# schmitt_rev2.net
KiCad netlist of a schematic drawn in EAGLE
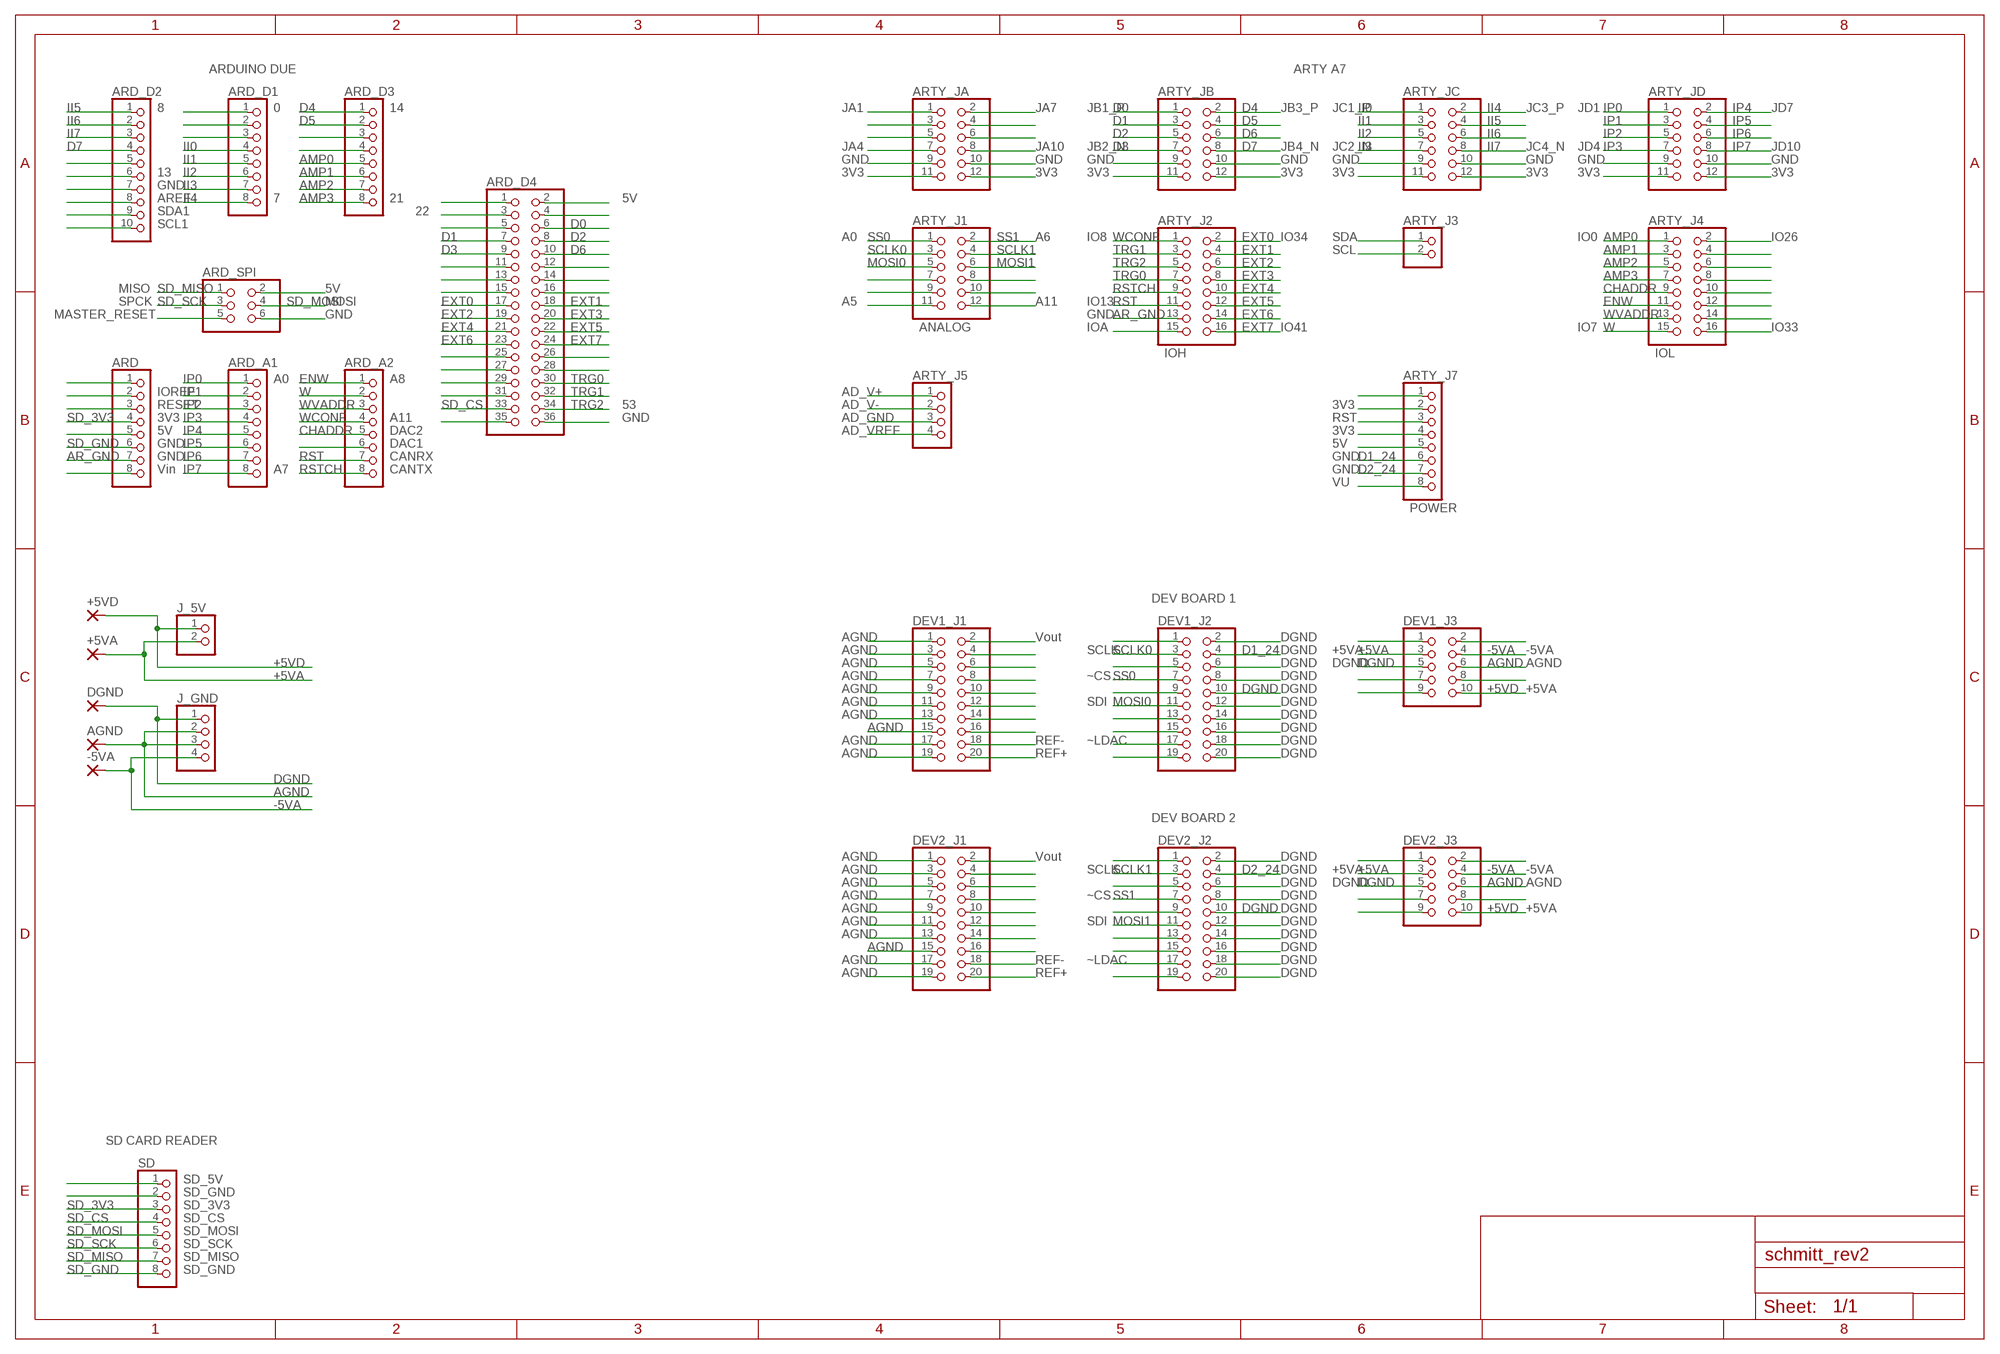
[diagram p0: schematic, sheet 1]

(export (version "E")
  (design (tool "Eeschema 10.0.6"))
  (components
    (comp (ref "+5VA")
      (value "2,15/1,0")
      (footprint "eagle-import:2,15_1,0")
      (libsource (lib "eagle-import") (part "2,15/1,0"))
    )
    (comp (ref "+5VD")
      (value "2,15/1,0")
      (footprint "eagle-import:2,15_1,0")
      (libsource (lib "eagle-import") (part "2,15/1,0"))
    )
    (comp (ref "-5VA")
      (value "2,15/1,0")
      (footprint "eagle-import:2,15_1,0")
      (libsource (lib "eagle-import") (part "2,15/1,0"))
    )
    (comp (ref "AGND")
      (value "2,15/1,0")
      (footprint "eagle-import:2,15_1,0")
      (libsource (lib "eagle-import") (part "2,15/1,0"))
    )
    (comp (ref "ARD")
      (value "PINHD-1X8")
      (footprint "eagle-import:1X08")
      (libsource (lib "eagle-import") (part "PINHD-1X8"))
    )
    (comp (ref "ARD_A1")
      (value "PINHD-1X8")
      (footprint "eagle-import:1X08")
      (libsource (lib "eagle-import") (part "PINHD-1X8"))
    )
    (comp (ref "ARD_A2")
      (value "PINHD-1X8")
      (footprint "eagle-import:1X08")
      (libsource (lib "eagle-import") (part "PINHD-1X8"))
    )
    (comp (ref "ARD_D1")
      (value "PINHD-1X8")
      (footprint "eagle-import:1X08")
      (libsource (lib "eagle-import") (part "PINHD-1X8"))
    )
    (comp (ref "ARD_D2")
      (value "PINHD-1X10")
      (footprint "eagle-import:1X10")
      (libsource (lib "eagle-import") (part "PINHD-1X10"))
    )
    (comp (ref "ARD_D3")
      (value "PINHD-1X8")
      (footprint "eagle-import:1X08")
      (libsource (lib "eagle-import") (part "PINHD-1X8"))
    )
    (comp (ref "ARD_D4")
      (value "PINHD-2X18")
      (footprint "eagle-import:2X18")
      (libsource (lib "eagle-import") (part "PINHD-2X18"))
    )
    (comp (ref "ARD_SPI")
      (value "PINHD-2X3")
      (footprint "eagle-import:2X03")
      (libsource (lib "eagle-import") (part "PINHD-2X3"))
    )
    (comp (ref "ARTY_J1")
      (value "PINHD-2X6")
      (footprint "eagle-import:2X06")
      (libsource (lib "eagle-import") (part "PINHD-2X6"))
    )
    (comp (ref "ARTY_J2")
      (value "PINHD-2X8")
      (footprint "eagle-import:2X08")
      (libsource (lib "eagle-import") (part "PINHD-2X8"))
    )
    (comp (ref "ARTY_J3")
      (value "PINHD-1X2")
      (footprint "eagle-import:1X02")
      (libsource (lib "eagle-import") (part "PINHD-1X2"))
    )
    (comp (ref "ARTY_J4")
      (value "PINHD-2X8")
      (footprint "eagle-import:2X08")
      (libsource (lib "eagle-import") (part "PINHD-2X8"))
    )
    (comp (ref "ARTY_J5")
      (value "PINHD-1X4")
      (footprint "eagle-import:1X04")
      (libsource (lib "eagle-import") (part "PINHD-1X4"))
    )
    (comp (ref "ARTY_J7")
      (value "PINHD-1X8")
      (footprint "eagle-import:1X08")
      (libsource (lib "eagle-import") (part "PINHD-1X8"))
    )
    (comp (ref "ARTY_JA")
      (value "PINHD-2X6")
      (footprint "eagle-import:2X06")
      (libsource (lib "eagle-import") (part "PINHD-2X6"))
    )
    (comp (ref "ARTY_JB")
      (value "PINHD-2X6")
      (footprint "eagle-import:2X06")
      (libsource (lib "eagle-import") (part "PINHD-2X6"))
    )
    (comp (ref "ARTY_JC")
      (value "PINHD-2X6")
      (footprint "eagle-import:2X06")
      (libsource (lib "eagle-import") (part "PINHD-2X6"))
    )
    (comp (ref "ARTY_JD")
      (value "PINHD-2X6")
      (footprint "eagle-import:2X06")
      (libsource (lib "eagle-import") (part "PINHD-2X6"))
    )
    (comp (ref "DEV1_J1")
      (value "PINHD-2X10")
      (footprint "eagle-import:2X10")
      (libsource (lib "eagle-import") (part "PINHD-2X10"))
    )
    (comp (ref "DEV1_J2")
      (value "PINHD-2X10")
      (footprint "eagle-import:2X10")
      (libsource (lib "eagle-import") (part "PINHD-2X10"))
    )
    (comp (ref "DEV1_J3")
      (value "PINHD-2X5")
      (footprint "eagle-import:2X05")
      (libsource (lib "eagle-import") (part "PINHD-2X5"))
    )
    (comp (ref "DEV2_J1")
      (value "PINHD-2X10")
      (footprint "eagle-import:2X10")
      (libsource (lib "eagle-import") (part "PINHD-2X10"))
    )
    (comp (ref "DEV2_J2")
      (value "PINHD-2X10")
      (footprint "eagle-import:2X10")
      (libsource (lib "eagle-import") (part "PINHD-2X10"))
    )
    (comp (ref "DEV2_J3")
      (value "PINHD-2X5")
      (footprint "eagle-import:2X05")
      (libsource (lib "eagle-import") (part "PINHD-2X5"))
    )
    (comp (ref "DGND")
      (value "2,15/1,0")
      (footprint "eagle-import:2,15_1,0")
      (libsource (lib "eagle-import") (part "2,15/1,0"))
    )
    (comp (ref "J_5V")
      (value "PINHD-1X2")
      (footprint "eagle-import:1X02")
      (libsource (lib "eagle-import") (part "PINHD-1X2"))
    )
    (comp (ref "J_GND")
      (value "PINHD-1X4")
      (footprint "eagle-import:1X04")
      (libsource (lib "eagle-import") (part "PINHD-1X4"))
    )
    (comp (ref "SD")
      (value "PINHD-1X8")
      (footprint "eagle-import:1X08")
      (libsource (lib "eagle-import") (part "PINHD-1X8"))
    )
  )
  (nets
    (net (code "1") (name "/+5VA") (class "Default")
      (node (ref "+5VA") (pin "1") (pinfunction "P_1") (pintype "passive"))
      (node (ref "DEV1_J3") (pin "3") (pinfunction "3_3") (pintype "passive"))
      (node (ref "DEV2_J3") (pin "3") (pinfunction "3_3") (pintype "passive"))
      (node (ref "J_5V") (pin "2") (pinfunction "2_2") (pintype "passive"))
    )
    (net (code "2") (name "/+5VD") (class "Default")
      (node (ref "+5VD") (pin "1") (pinfunction "P_1") (pintype "passive"))
      (node (ref "DEV1_J3") (pin "10") (pinfunction "10_10") (pintype "passive"))
      (node (ref "DEV2_J3") (pin "10") (pinfunction "10_10") (pintype "passive"))
      (node (ref "J_5V") (pin "1") (pinfunction "1_1") (pintype "passive"))
    )
    (net (code "3") (name "/-5VA") (class "Default")
      (node (ref "-5VA") (pin "1") (pinfunction "P_1") (pintype "passive"))
      (node (ref "DEV1_J3") (pin "4") (pinfunction "4_4") (pintype "passive"))
      (node (ref "DEV2_J3") (pin "4") (pinfunction "4_4") (pintype "passive"))
      (node (ref "J_GND") (pin "4") (pinfunction "4_4") (pintype "passive"))
    )
    (net (code "4") (name "/AGND") (class "Default")
      (node (ref "AGND") (pin "1") (pinfunction "P_1") (pintype "passive"))
      (node (ref "DEV1_J1") (pin "15") (pinfunction "15_15") (pintype "passive"))
      (node (ref "DEV1_J3") (pin "6") (pinfunction "6_6") (pintype "passive"))
      (node (ref "DEV2_J1") (pin "15") (pinfunction "15_15") (pintype "passive"))
      (node (ref "DEV2_J3") (pin "6") (pinfunction "6_6") (pintype "passive"))
      (node (ref "J_GND") (pin "2") (pinfunction "2_2") (pintype "passive"))
      (node (ref "J_GND") (pin "3") (pinfunction "3_3") (pintype "passive"))
    )
    (net (code "5") (name "/AMP0") (class "Default")
      (node (ref "ARD_D3") (pin "5") (pinfunction "5_5") (pintype "passive"))
      (node (ref "ARTY_J4") (pin "1") (pinfunction "1_1") (pintype "passive"))
    )
    (net (code "6") (name "/AMP1") (class "Default")
      (node (ref "ARD_D3") (pin "6") (pinfunction "6_6") (pintype "passive"))
      (node (ref "ARTY_J4") (pin "3") (pinfunction "3_3") (pintype "passive"))
    )
    (net (code "7") (name "/AMP2") (class "Default")
      (node (ref "ARD_D3") (pin "7") (pinfunction "7_7") (pintype "passive"))
      (node (ref "ARTY_J4") (pin "5") (pinfunction "5_5") (pintype "passive"))
    )
    (net (code "8") (name "/AMP3") (class "Default")
      (node (ref "ARD_D3") (pin "8") (pinfunction "8_8") (pintype "passive"))
      (node (ref "ARTY_J4") (pin "7") (pinfunction "7_7") (pintype "passive"))
    )
    (net (code "9") (name "/AR_GND") (class "Default")
      (node (ref "ARD") (pin "7") (pinfunction "7_7") (pintype "passive"))
      (node (ref "ARTY_J2") (pin "13") (pinfunction "13_13") (pintype "passive"))
    )
    (net (code "10") (name "/CHADDR") (class "Default")
      (node (ref "ARD_A2") (pin "5") (pinfunction "5_5") (pintype "passive"))
      (node (ref "ARTY_J4") (pin "9") (pinfunction "9_9") (pintype "passive"))
    )
    (net (code "11") (name "/D0") (class "Default")
      (node (ref "ARD_D4") (pin "6") (pinfunction "6_6") (pintype "passive"))
      (node (ref "ARTY_JB") (pin "1") (pinfunction "1_1") (pintype "passive"))
    )
    (net (code "12") (name "/D1") (class "Default")
      (node (ref "ARD_D4") (pin "7") (pinfunction "7_7") (pintype "passive"))
      (node (ref "ARTY_JB") (pin "3") (pinfunction "3_3") (pintype "passive"))
    )
    (net (code "13") (name "/D1_24") (class "Default")
      (node (ref "ARTY_J7") (pin "6") (pinfunction "6_6") (pintype "passive"))
      (node (ref "DEV1_J2") (pin "4") (pinfunction "4_4") (pintype "passive"))
    )
    (net (code "14") (name "/D2") (class "Default")
      (node (ref "ARD_D4") (pin "8") (pinfunction "8_8") (pintype "passive"))
      (node (ref "ARTY_JB") (pin "5") (pinfunction "5_5") (pintype "passive"))
    )
    (net (code "15") (name "/D2_24") (class "Default")
      (node (ref "ARTY_J7") (pin "7") (pinfunction "7_7") (pintype "passive"))
      (node (ref "DEV2_J2") (pin "4") (pinfunction "4_4") (pintype "passive"))
    )
    (net (code "16") (name "/D3") (class "Default")
      (node (ref "ARD_D4") (pin "9") (pinfunction "9_9") (pintype "passive"))
      (node (ref "ARTY_JB") (pin "7") (pinfunction "7_7") (pintype "passive"))
    )
    (net (code "17") (name "/D4") (class "Default")
      (node (ref "ARD_D3") (pin "1") (pinfunction "1_1") (pintype "passive"))
      (node (ref "ARTY_JB") (pin "2") (pinfunction "2_2") (pintype "passive"))
    )
    (net (code "18") (name "/D5") (class "Default")
      (node (ref "ARD_D3") (pin "2") (pinfunction "2_2") (pintype "passive"))
      (node (ref "ARTY_JB") (pin "4") (pinfunction "4_4") (pintype "passive"))
    )
    (net (code "19") (name "/D6") (class "Default")
      (node (ref "ARD_D4") (pin "10") (pinfunction "10_10") (pintype "passive"))
      (node (ref "ARTY_JB") (pin "6") (pinfunction "6_6") (pintype "passive"))
    )
    (net (code "20") (name "/D7") (class "Default")
      (node (ref "ARD_D2") (pin "4") (pinfunction "4_4") (pintype "passive"))
      (node (ref "ARTY_JB") (pin "8") (pinfunction "8_8") (pintype "passive"))
    )
    (net (code "21") (name "/DGND") (class "Default")
      (node (ref "DEV1_J2") (pin "10") (pinfunction "10_10") (pintype "passive"))
      (node (ref "DEV1_J3") (pin "5") (pinfunction "5_5") (pintype "passive"))
      (node (ref "DEV2_J2") (pin "10") (pinfunction "10_10") (pintype "passive"))
      (node (ref "DEV2_J3") (pin "5") (pinfunction "5_5") (pintype "passive"))
      (node (ref "DGND") (pin "1") (pinfunction "P_1") (pintype "passive"))
      (node (ref "J_GND") (pin "1") (pinfunction "1_1") (pintype "passive"))
    )
    (net (code "22") (name "/ENW") (class "Default")
      (node (ref "ARD_A2") (pin "1") (pinfunction "1_1") (pintype "passive"))
      (node (ref "ARTY_J4") (pin "11") (pinfunction "11_11") (pintype "passive"))
    )
    (net (code "23") (name "/EXT0") (class "Default")
      (node (ref "ARD_D4") (pin "17") (pinfunction "17_17") (pintype "passive"))
      (node (ref "ARTY_J2") (pin "2") (pinfunction "2_2") (pintype "passive"))
    )
    (net (code "24") (name "/EXT1") (class "Default")
      (node (ref "ARD_D4") (pin "18") (pinfunction "18_18") (pintype "passive"))
      (node (ref "ARTY_J2") (pin "4") (pinfunction "4_4") (pintype "passive"))
    )
    (net (code "25") (name "/EXT2") (class "Default")
      (node (ref "ARD_D4") (pin "19") (pinfunction "19_19") (pintype "passive"))
      (node (ref "ARTY_J2") (pin "6") (pinfunction "6_6") (pintype "passive"))
    )
    (net (code "26") (name "/EXT3") (class "Default")
      (node (ref "ARD_D4") (pin "20") (pinfunction "20_20") (pintype "passive"))
      (node (ref "ARTY_J2") (pin "8") (pinfunction "8_8") (pintype "passive"))
    )
    (net (code "27") (name "/EXT4") (class "Default")
      (node (ref "ARD_D4") (pin "21") (pinfunction "21_21") (pintype "passive"))
      (node (ref "ARTY_J2") (pin "10") (pinfunction "10_10") (pintype "passive"))
    )
    (net (code "28") (name "/EXT5") (class "Default")
      (node (ref "ARD_D4") (pin "22") (pinfunction "22_22") (pintype "passive"))
      (node (ref "ARTY_J2") (pin "12") (pinfunction "12_12") (pintype "passive"))
    )
    (net (code "29") (name "/EXT6") (class "Default")
      (node (ref "ARD_D4") (pin "23") (pinfunction "23_23") (pintype "passive"))
      (node (ref "ARTY_J2") (pin "14") (pinfunction "14_14") (pintype "passive"))
    )
    (net (code "30") (name "/EXT7") (class "Default")
      (node (ref "ARD_D4") (pin "24") (pinfunction "24_24") (pintype "passive"))
      (node (ref "ARTY_J2") (pin "16") (pinfunction "16_16") (pintype "passive"))
    )
    (net (code "31") (name "/II0") (class "Default")
      (node (ref "ARD_D1") (pin "4") (pinfunction "4_4") (pintype "passive"))
      (node (ref "ARTY_JC") (pin "1") (pinfunction "1_1") (pintype "passive"))
    )
    (net (code "32") (name "/II1") (class "Default")
      (node (ref "ARD_D1") (pin "5") (pinfunction "5_5") (pintype "passive"))
      (node (ref "ARTY_JC") (pin "3") (pinfunction "3_3") (pintype "passive"))
    )
    (net (code "33") (name "/II2") (class "Default")
      (node (ref "ARD_D1") (pin "6") (pinfunction "6_6") (pintype "passive"))
      (node (ref "ARTY_JC") (pin "5") (pinfunction "5_5") (pintype "passive"))
    )
    (net (code "34") (name "/II3") (class "Default")
      (node (ref "ARD_D1") (pin "7") (pinfunction "7_7") (pintype "passive"))
      (node (ref "ARTY_JC") (pin "7") (pinfunction "7_7") (pintype "passive"))
    )
    (net (code "35") (name "/II4") (class "Default")
      (node (ref "ARD_D1") (pin "8") (pinfunction "8_8") (pintype "passive"))
      (node (ref "ARTY_JC") (pin "2") (pinfunction "2_2") (pintype "passive"))
    )
    (net (code "36") (name "/II5") (class "Default")
      (node (ref "ARD_D2") (pin "1") (pinfunction "1_1") (pintype "passive"))
      (node (ref "ARTY_JC") (pin "4") (pinfunction "4_4") (pintype "passive"))
    )
    (net (code "37") (name "/II6") (class "Default")
      (node (ref "ARD_D2") (pin "2") (pinfunction "2_2") (pintype "passive"))
      (node (ref "ARTY_JC") (pin "6") (pinfunction "6_6") (pintype "passive"))
    )
    (net (code "38") (name "/II7") (class "Default")
      (node (ref "ARD_D2") (pin "3") (pinfunction "3_3") (pintype "passive"))
      (node (ref "ARTY_JC") (pin "8") (pinfunction "8_8") (pintype "passive"))
    )
    (net (code "39") (name "/IP0") (class "Default")
      (node (ref "ARD_A1") (pin "1") (pinfunction "1_1") (pintype "passive"))
      (node (ref "ARTY_JD") (pin "1") (pinfunction "1_1") (pintype "passive"))
    )
    (net (code "40") (name "/IP1") (class "Default")
      (node (ref "ARD_A1") (pin "2") (pinfunction "2_2") (pintype "passive"))
      (node (ref "ARTY_JD") (pin "3") (pinfunction "3_3") (pintype "passive"))
    )
    (net (code "41") (name "/IP2") (class "Default")
      (node (ref "ARD_A1") (pin "3") (pinfunction "3_3") (pintype "passive"))
      (node (ref "ARTY_JD") (pin "5") (pinfunction "5_5") (pintype "passive"))
    )
    (net (code "42") (name "/IP3") (class "Default")
      (node (ref "ARD_A1") (pin "4") (pinfunction "4_4") (pintype "passive"))
      (node (ref "ARTY_JD") (pin "7") (pinfunction "7_7") (pintype "passive"))
    )
    (net (code "43") (name "/IP4") (class "Default")
      (node (ref "ARD_A1") (pin "5") (pinfunction "5_5") (pintype "passive"))
      (node (ref "ARTY_JD") (pin "2") (pinfunction "2_2") (pintype "passive"))
    )
    (net (code "44") (name "/IP5") (class "Default")
      (node (ref "ARD_A1") (pin "6") (pinfunction "6_6") (pintype "passive"))
      (node (ref "ARTY_JD") (pin "4") (pinfunction "4_4") (pintype "passive"))
    )
    (net (code "45") (name "/IP6") (class "Default")
      (node (ref "ARD_A1") (pin "7") (pinfunction "7_7") (pintype "passive"))
      (node (ref "ARTY_JD") (pin "6") (pinfunction "6_6") (pintype "passive"))
    )
    (net (code "46") (name "/IP7") (class "Default")
      (node (ref "ARD_A1") (pin "8") (pinfunction "8_8") (pintype "passive"))
      (node (ref "ARTY_JD") (pin "8") (pinfunction "8_8") (pintype "passive"))
    )
    (net (code "47") (name "/MOSI0") (class "Default")
      (node (ref "ARTY_J1") (pin "5") (pinfunction "5_5") (pintype "passive"))
      (node (ref "DEV1_J2") (pin "11") (pinfunction "11_11") (pintype "passive"))
    )
    (net (code "48") (name "/MOSI1") (class "Default")
      (node (ref "ARTY_J1") (pin "6") (pinfunction "6_6") (pintype "passive"))
      (node (ref "DEV2_J2") (pin "11") (pinfunction "11_11") (pintype "passive"))
    )
    (net (code "49") (name "/RST") (class "Default")
      (node (ref "ARD_A2") (pin "7") (pinfunction "7_7") (pintype "passive"))
      (node (ref "ARTY_J2") (pin "11") (pinfunction "11_11") (pintype "passive"))
    )
    (net (code "50") (name "/RSTCH") (class "Default")
      (node (ref "ARD_A2") (pin "8") (pinfunction "8_8") (pintype "passive"))
      (node (ref "ARTY_J2") (pin "9") (pinfunction "9_9") (pintype "passive"))
    )
    (net (code "51") (name "/SCLK0") (class "Default")
      (node (ref "ARTY_J1") (pin "3") (pinfunction "3_3") (pintype "passive"))
      (node (ref "DEV1_J2") (pin "3") (pinfunction "3_3") (pintype "passive"))
    )
    (net (code "52") (name "/SCLK1") (class "Default")
      (node (ref "ARTY_J1") (pin "4") (pinfunction "4_4") (pintype "passive"))
      (node (ref "DEV2_J2") (pin "3") (pinfunction "3_3") (pintype "passive"))
    )
    (net (code "53") (name "/SD_3V3") (class "Default")
      (node (ref "ARD") (pin "4") (pinfunction "4_4") (pintype "passive"))
      (node (ref "SD") (pin "3") (pinfunction "3_3") (pintype "passive"))
    )
    (net (code "54") (name "/SD_CS") (class "Default")
      (node (ref "ARD_D4") (pin "33") (pinfunction "33_33") (pintype "passive"))
      (node (ref "SD") (pin "4") (pinfunction "4_4") (pintype "passive"))
    )
    (net (code "55") (name "/SD_GND") (class "Default")
      (node (ref "ARD") (pin "6") (pinfunction "6_6") (pintype "passive"))
      (node (ref "SD") (pin "8") (pinfunction "8_8") (pintype "passive"))
    )
    (net (code "56") (name "/SD_MISO") (class "Default")
      (node (ref "ARD_SPI") (pin "1") (pinfunction "1_1") (pintype "passive"))
      (node (ref "SD") (pin "7") (pinfunction "7_7") (pintype "passive"))
    )
    (net (code "57") (name "/SD_MOSI") (class "Default")
      (node (ref "ARD_SPI") (pin "4") (pinfunction "4_4") (pintype "passive"))
      (node (ref "SD") (pin "5") (pinfunction "5_5") (pintype "passive"))
    )
    (net (code "58") (name "/SD_SCK") (class "Default")
      (node (ref "ARD_SPI") (pin "3") (pinfunction "3_3") (pintype "passive"))
      (node (ref "SD") (pin "6") (pinfunction "6_6") (pintype "passive"))
    )
    (net (code "59") (name "/SS0") (class "Default")
      (node (ref "ARTY_J1") (pin "1") (pinfunction "1_1") (pintype "passive"))
      (node (ref "DEV1_J2") (pin "7") (pinfunction "7_7") (pintype "passive"))
    )
    (net (code "60") (name "/SS1") (class "Default")
      (node (ref "ARTY_J1") (pin "2") (pinfunction "2_2") (pintype "passive"))
      (node (ref "DEV2_J2") (pin "7") (pinfunction "7_7") (pintype "passive"))
    )
    (net (code "61") (name "/TRG0") (class "Default")
      (node (ref "ARD_D4") (pin "30") (pinfunction "30_30") (pintype "passive"))
      (node (ref "ARTY_J2") (pin "7") (pinfunction "7_7") (pintype "passive"))
    )
    (net (code "62") (name "/TRG1") (class "Default")
      (node (ref "ARD_D4") (pin "32") (pinfunction "32_32") (pintype "passive"))
      (node (ref "ARTY_J2") (pin "3") (pinfunction "3_3") (pintype "passive"))
    )
    (net (code "63") (name "/TRG2") (class "Default")
      (node (ref "ARD_D4") (pin "34") (pinfunction "34_34") (pintype "passive"))
      (node (ref "ARTY_J2") (pin "5") (pinfunction "5_5") (pintype "passive"))
    )
    (net (code "64") (name "/W") (class "Default")
      (node (ref "ARD_A2") (pin "2") (pinfunction "2_2") (pintype "passive"))
      (node (ref "ARTY_J4") (pin "15") (pinfunction "15_15") (pintype "passive"))
    )
    (net (code "65") (name "/WCONF") (class "Default")
      (node (ref "ARD_A2") (pin "4") (pinfunction "4_4") (pintype "passive"))
      (node (ref "ARTY_J2") (pin "1") (pinfunction "1_1") (pintype "passive"))
    )
    (net (code "66") (name "/WVADDR") (class "Default")
      (node (ref "ARD_A2") (pin "3") (pinfunction "3_3") (pintype "passive"))
      (node (ref "ARTY_J4") (pin "13") (pinfunction "13_13") (pintype "passive"))
    )
    (net (code "67") (name "unconnected-(ARD-Pad1)") (class "Default")
      (node (ref "ARD") (pin "1") (pinfunction "1_1") (pintype "passive"))
    )
    (net (code "68") (name "unconnected-(ARD-Pad2)") (class "Default")
      (node (ref "ARD") (pin "2") (pinfunction "2_2") (pintype "passive"))
    )
    (net (code "69") (name "unconnected-(ARD-Pad3)") (class "Default")
      (node (ref "ARD") (pin "3") (pinfunction "3_3") (pintype "passive"))
    )
    (net (code "70") (name "unconnected-(ARD-Pad5)") (class "Default")
      (node (ref "ARD") (pin "5") (pinfunction "5_5") (pintype "passive"))
    )
    (net (code "71") (name "unconnected-(ARD-Pad8)") (class "Default")
      (node (ref "ARD") (pin "8") (pinfunction "8_8") (pintype "passive"))
    )
    (net (code "72") (name "unconnected-(ARD_A2-Pad6)") (class "Default")
      (node (ref "ARD_A2") (pin "6") (pinfunction "6_6") (pintype "passive"))
    )
    (net (code "73") (name "unconnected-(ARD_D1-Pad1)") (class "Default")
      (node (ref "ARD_D1") (pin "1") (pinfunction "1_1") (pintype "passive"))
    )
    (net (code "74") (name "unconnected-(ARD_D1-Pad2)") (class "Default")
      (node (ref "ARD_D1") (pin "2") (pinfunction "2_2") (pintype "passive"))
    )
    (net (code "75") (name "unconnected-(ARD_D1-Pad3)") (class "Default")
      (node (ref "ARD_D1") (pin "3") (pinfunction "3_3") (pintype "passive"))
    )
    (net (code "76") (name "unconnected-(ARD_D2-Pad5)") (class "Default")
      (node (ref "ARD_D2") (pin "5") (pinfunction "5_5") (pintype "passive"))
    )
    (net (code "77") (name "unconnected-(ARD_D2-Pad6)") (class "Default")
      (node (ref "ARD_D2") (pin "6") (pinfunction "6_6") (pintype "passive"))
    )
    (net (code "78") (name "unconnected-(ARD_D2-Pad7)") (class "Default")
      (node (ref "ARD_D2") (pin "7") (pinfunction "7_7") (pintype "passive"))
    )
    (net (code "79") (name "unconnected-(ARD_D2-Pad8)") (class "Default")
      (node (ref "ARD_D2") (pin "8") (pinfunction "8_8") (pintype "passive"))
    )
    (net (code "80") (name "unconnected-(ARD_D2-Pad9)") (class "Default")
      (node (ref "ARD_D2") (pin "9") (pinfunction "9_9") (pintype "passive"))
    )
    (net (code "81") (name "unconnected-(ARD_D2-Pad10)") (class "Default")
      (node (ref "ARD_D2") (pin "10") (pinfunction "10_10") (pintype "passive"))
    )
    (net (code "82") (name "unconnected-(ARD_D3-Pad3)") (class "Default")
      (node (ref "ARD_D3") (pin "3") (pinfunction "3_3") (pintype "passive"))
    )
    (net (code "83") (name "unconnected-(ARD_D3-Pad4)") (class "Default")
      (node (ref "ARD_D3") (pin "4") (pinfunction "4_4") (pintype "passive"))
    )
    (net (code "84") (name "unconnected-(ARD_D4-Pad1)") (class "Default")
      (node (ref "ARD_D4") (pin "1") (pinfunction "1_1") (pintype "passive"))
    )
    (net (code "85") (name "unconnected-(ARD_D4-Pad2)") (class "Default")
      (node (ref "ARD_D4") (pin "2") (pinfunction "2_2") (pintype "passive"))
    )
    (net (code "86") (name "unconnected-(ARD_D4-Pad3)") (class "Default")
      (node (ref "ARD_D4") (pin "3") (pinfunction "3_3") (pintype "passive"))
    )
    (net (code "87") (name "unconnected-(ARD_D4-Pad4)") (class "Default")
      (node (ref "ARD_D4") (pin "4") (pinfunction "4_4") (pintype "passive"))
    )
    (net (code "88") (name "unconnected-(ARD_D4-Pad5)") (class "Default")
      (node (ref "ARD_D4") (pin "5") (pinfunction "5_5") (pintype "passive"))
    )
    (net (code "89") (name "unconnected-(ARD_D4-Pad11)") (class "Default")
      (node (ref "ARD_D4") (pin "11") (pinfunction "11_11") (pintype "passive"))
    )
    (net (code "90") (name "unconnected-(ARD_D4-Pad12)") (class "Default")
      (node (ref "ARD_D4") (pin "12") (pinfunction "12_12") (pintype "passive"))
    )
    (net (code "91") (name "unconnected-(ARD_D4-Pad13)") (class "Default")
      (node (ref "ARD_D4") (pin "13") (pinfunction "13_13") (pintype "passive"))
    )
    (net (code "92") (name "unconnected-(ARD_D4-Pad14)") (class "Default")
      (node (ref "ARD_D4") (pin "14") (pinfunction "14_14") (pintype "passive"))
    )
    (net (code "93") (name "unconnected-(ARD_D4-Pad15)") (class "Default")
      (node (ref "ARD_D4") (pin "15") (pinfunction "15_15") (pintype "passive"))
    )
    (net (code "94") (name "unconnected-(ARD_D4-Pad16)") (class "Default")
      (node (ref "ARD_D4") (pin "16") (pinfunction "16_16") (pintype "passive"))
    )
    (net (code "95") (name "unconnected-(ARD_D4-Pad25)") (class "Default")
      (node (ref "ARD_D4") (pin "25") (pinfunction "25_25") (pintype "passive"))
    )
    (net (code "96") (name "unconnected-(ARD_D4-Pad26)") (class "Default")
      (node (ref "ARD_D4") (pin "26") (pinfunction "26_26") (pintype "passive"))
    )
    (net (code "97") (name "unconnected-(ARD_D4-Pad27)") (class "Default")
      (node (ref "ARD_D4") (pin "27") (pinfunction "27_27") (pintype "passive"))
    )
    (net (code "98") (name "unconnected-(ARD_D4-Pad28)") (class "Default")
      (node (ref "ARD_D4") (pin "28") (pinfunction "28_28") (pintype "passive"))
    )
    (net (code "99") (name "unconnected-(ARD_D4-Pad29)") (class "Default")
      (node (ref "ARD_D4") (pin "29") (pinfunction "29_29") (pintype "passive"))
    )
    (net (code "100") (name "unconnected-(ARD_D4-Pad31)") (class "Default")
      (node (ref "ARD_D4") (pin "31") (pinfunction "31_31") (pintype "passive"))
    )
    (net (code "101") (name "unconnected-(ARD_D4-Pad35)") (class "Default")
      (node (ref "ARD_D4") (pin "35") (pinfunction "35_35") (pintype "passive"))
    )
    (net (code "102") (name "unconnected-(ARD_D4-Pad36)") (class "Default")
      (node (ref "ARD_D4") (pin "36") (pinfunction "36_36") (pintype "passive"))
    )
    (net (code "103") (name "unconnected-(ARD_SPI-Pad2)") (class "Default")
      (node (ref "ARD_SPI") (pin "2") (pinfunction "2_2") (pintype "passive"))
    )
    (net (code "104") (name "unconnected-(ARD_SPI-Pad5)") (class "Default")
      (node (ref "ARD_SPI") (pin "5") (pinfunction "5_5") (pintype "passive"))
    )
    (net (code "105") (name "unconnected-(ARD_SPI-Pad6)") (class "Default")
      (node (ref "ARD_SPI") (pin "6") (pinfunction "6_6") (pintype "passive"))
    )
    (net (code "106") (name "unconnected-(ARTY_J1-Pad7)") (class "Default")
      (node (ref "ARTY_J1") (pin "7") (pinfunction "7_7") (pintype "passive"))
    )
    (net (code "107") (name "unconnected-(ARTY_J1-Pad8)") (class "Default")
      (node (ref "ARTY_J1") (pin "8") (pinfunction "8_8") (pintype "passive"))
    )
    (net (code "108") (name "unconnected-(ARTY_J1-Pad9)") (class "Default")
      (node (ref "ARTY_J1") (pin "9") (pinfunction "9_9") (pintype "passive"))
    )
    (net (code "109") (name "unconnected-(ARTY_J1-Pad10)") (class "Default")
      (node (ref "ARTY_J1") (pin "10") (pinfunction "10_10") (pintype "passive"))
    )
    (net (code "110") (name "unconnected-(ARTY_J1-Pad11)") (class "Default")
      (node (ref "ARTY_J1") (pin "11") (pinfunction "11_11") (pintype "passive"))
    )
    (net (code "111") (name "unconnected-(ARTY_J1-Pad12)") (class "Default")
      (node (ref "ARTY_J1") (pin "12") (pinfunction "12_12") (pintype "passive"))
    )
    (net (code "112") (name "unconnected-(ARTY_J2-Pad15)") (class "Default")
      (node (ref "ARTY_J2") (pin "15") (pinfunction "15_15") (pintype "passive"))
    )
    (net (code "113") (name "unconnected-(ARTY_J3-Pad1)") (class "Default")
      (node (ref "ARTY_J3") (pin "1") (pinfunction "1_1") (pintype "passive"))
    )
    (net (code "114") (name "unconnected-(ARTY_J3-Pad2)") (class "Default")
      (node (ref "ARTY_J3") (pin "2") (pinfunction "2_2") (pintype "passive"))
    )
    (net (code "115") (name "unconnected-(ARTY_J4-Pad2)") (class "Default")
      (node (ref "ARTY_J4") (pin "2") (pinfunction "2_2") (pintype "passive"))
    )
    (net (code "116") (name "unconnected-(ARTY_J4-Pad4)") (class "Default")
      (node (ref "ARTY_J4") (pin "4") (pinfunction "4_4") (pintype "passive"))
    )
    (net (code "117") (name "unconnected-(ARTY_J4-Pad6)") (class "Default")
      (node (ref "ARTY_J4") (pin "6") (pinfunction "6_6") (pintype "passive"))
    )
    (net (code "118") (name "unconnected-(ARTY_J4-Pad8)") (class "Default")
      (node (ref "ARTY_J4") (pin "8") (pinfunction "8_8") (pintype "passive"))
    )
    (net (code "119") (name "unconnected-(ARTY_J4-Pad10)") (class "Default")
      (node (ref "ARTY_J4") (pin "10") (pinfunction "10_10") (pintype "passive"))
    )
    (net (code "120") (name "unconnected-(ARTY_J4-Pad12)") (class "Default")
      (node (ref "ARTY_J4") (pin "12") (pinfunction "12_12") (pintype "passive"))
    )
    (net (code "121") (name "unconnected-(ARTY_J4-Pad14)") (class "Default")
      (node (ref "ARTY_J4") (pin "14") (pinfunction "14_14") (pintype "passive"))
    )
    (net (code "122") (name "unconnected-(ARTY_J4-Pad16)") (class "Default")
      (node (ref "ARTY_J4") (pin "16") (pinfunction "16_16") (pintype "passive"))
    )
    (net (code "123") (name "unconnected-(ARTY_J5-Pad1)") (class "Default")
      (node (ref "ARTY_J5") (pin "1") (pinfunction "1_1") (pintype "passive"))
    )
    (net (code "124") (name "unconnected-(ARTY_J5-Pad2)") (class "Default")
      (node (ref "ARTY_J5") (pin "2") (pinfunction "2_2") (pintype "passive"))
    )
    (net (code "125") (name "unconnected-(ARTY_J5-Pad3)") (class "Default")
      (node (ref "ARTY_J5") (pin "3") (pinfunction "3_3") (pintype "passive"))
    )
    (net (code "126") (name "unconnected-(ARTY_J5-Pad4)") (class "Default")
      (node (ref "ARTY_J5") (pin "4") (pinfunction "4_4") (pintype "passive"))
    )
    (net (code "127") (name "unconnected-(ARTY_J7-Pad1)") (class "Default")
      (node (ref "ARTY_J7") (pin "1") (pinfunction "1_1") (pintype "passive"))
    )
    (net (code "128") (name "unconnected-(ARTY_J7-Pad2)") (class "Default")
      (node (ref "ARTY_J7") (pin "2") (pinfunction "2_2") (pintype "passive"))
    )
    (net (code "129") (name "unconnected-(ARTY_J7-Pad3)") (class "Default")
      (node (ref "ARTY_J7") (pin "3") (pinfunction "3_3") (pintype "passive"))
    )
    (net (code "130") (name "unconnected-(ARTY_J7-Pad4)") (class "Default")
      (node (ref "ARTY_J7") (pin "4") (pinfunction "4_4") (pintype "passive"))
    )
    (net (code "131") (name "unconnected-(ARTY_J7-Pad5)") (class "Default")
      (node (ref "ARTY_J7") (pin "5") (pinfunction "5_5") (pintype "passive"))
    )
    (net (code "132") (name "unconnected-(ARTY_J7-Pad8)") (class "Default")
      (node (ref "ARTY_J7") (pin "8") (pinfunction "8_8") (pintype "passive"))
    )
    (net (code "133") (name "unconnected-(ARTY_JA-Pad1)") (class "Default")
      (node (ref "ARTY_JA") (pin "1") (pinfunction "1_1") (pintype "passive"))
    )
    (net (code "134") (name "unconnected-(ARTY_JA-Pad2)") (class "Default")
      (node (ref "ARTY_JA") (pin "2") (pinfunction "2_2") (pintype "passive"))
    )
    (net (code "135") (name "unconnected-(ARTY_JA-Pad3)") (class "Default")
      (node (ref "ARTY_JA") (pin "3") (pinfunction "3_3") (pintype "passive"))
    )
    (net (code "136") (name "unconnected-(ARTY_JA-Pad4)") (class "Default")
      (node (ref "ARTY_JA") (pin "4") (pinfunction "4_4") (pintype "passive"))
    )
    (net (code "137") (name "unconnected-(ARTY_JA-Pad5)") (class "Default")
      (node (ref "ARTY_JA") (pin "5") (pinfunction "5_5") (pintype "passive"))
    )
    (net (code "138") (name "unconnected-(ARTY_JA-Pad6)") (class "Default")
      (node (ref "ARTY_JA") (pin "6") (pinfunction "6_6") (pintype "passive"))
    )
    (net (code "139") (name "unconnected-(ARTY_JA-Pad7)") (class "Default")
      (node (ref "ARTY_JA") (pin "7") (pinfunction "7_7") (pintype "passive"))
    )
    (net (code "140") (name "unconnected-(ARTY_JA-Pad8)") (class "Default")
      (node (ref "ARTY_JA") (pin "8") (pinfunction "8_8") (pintype "passive"))
    )
    (net (code "141") (name "unconnected-(ARTY_JA-Pad9)") (class "Default")
      (node (ref "ARTY_JA") (pin "9") (pinfunction "9_9") (pintype "passive"))
    )
    (net (code "142") (name "unconnected-(ARTY_JA-Pad10)") (class "Default")
      (node (ref "ARTY_JA") (pin "10") (pinfunction "10_10") (pintype "passive"))
    )
    (net (code "143") (name "unconnected-(ARTY_JA-Pad11)") (class "Default")
      (node (ref "ARTY_JA") (pin "11") (pinfunction "11_11") (pintype "passive"))
    )
    (net (code "144") (name "unconnected-(ARTY_JA-Pad12)") (class "Default")
      (node (ref "ARTY_JA") (pin "12") (pinfunction "12_12") (pintype "passive"))
    )
    (net (code "145") (name "unconnected-(ARTY_JB-Pad9)") (class "Default")
      (node (ref "ARTY_JB") (pin "9") (pinfunction "9_9") (pintype "passive"))
    )
    (net (code "146") (name "unconnected-(ARTY_JB-Pad10)") (class "Default")
      (node (ref "ARTY_JB") (pin "10") (pinfunction "10_10") (pintype "passive"))
    )
    (net (code "147") (name "unconnected-(ARTY_JB-Pad11)") (class "Default")
      (node (ref "ARTY_JB") (pin "11") (pinfunction "11_11") (pintype "passive"))
    )
    (net (code "148") (name "unconnected-(ARTY_JB-Pad12)") (class "Default")
      (node (ref "ARTY_JB") (pin "12") (pinfunction "12_12") (pintype "passive"))
    )
    (net (code "149") (name "unconnected-(ARTY_JC-Pad9)") (class "Default")
      (node (ref "ARTY_JC") (pin "9") (pinfunction "9_9") (pintype "passive"))
    )
    (net (code "150") (name "unconnected-(ARTY_JC-Pad10)") (class "Default")
      (node (ref "ARTY_JC") (pin "10") (pinfunction "10_10") (pintype "passive"))
    )
    (net (code "151") (name "unconnected-(ARTY_JC-Pad11)") (class "Default")
      (node (ref "ARTY_JC") (pin "11") (pinfunction "11_11") (pintype "passive"))
    )
    (net (code "152") (name "unconnected-(ARTY_JC-Pad12)") (class "Default")
      (node (ref "ARTY_JC") (pin "12") (pinfunction "12_12") (pintype "passive"))
    )
    (net (code "153") (name "unconnected-(ARTY_JD-Pad9)") (class "Default")
      (node (ref "ARTY_JD") (pin "9") (pinfunction "9_9") (pintype "passive"))
    )
    (net (code "154") (name "unconnected-(ARTY_JD-Pad10)") (class "Default")
      (node (ref "ARTY_JD") (pin "10") (pinfunction "10_10") (pintype "passive"))
    )
    (net (code "155") (name "unconnected-(ARTY_JD-Pad11)") (class "Default")
      (node (ref "ARTY_JD") (pin "11") (pinfunction "11_11") (pintype "passive"))
    )
    (net (code "156") (name "unconnected-(ARTY_JD-Pad12)") (class "Default")
      (node (ref "ARTY_JD") (pin "12") (pinfunction "12_12") (pintype "passive"))
    )
    (net (code "157") (name "unconnected-(DEV1_J1-Pad1)") (class "Default")
      (node (ref "DEV1_J1") (pin "1") (pinfunction "1_1") (pintype "passive"))
    )
    (net (code "158") (name "unconnected-(DEV1_J1-Pad2)") (class "Default")
      (node (ref "DEV1_J1") (pin "2") (pinfunction "2_2") (pintype "passive"))
    )
    (net (code "159") (name "unconnected-(DEV1_J1-Pad3)") (class "Default")
      (node (ref "DEV1_J1") (pin "3") (pinfunction "3_3") (pintype "passive"))
    )
    (net (code "160") (name "unconnected-(DEV1_J1-Pad4)") (class "Default")
      (node (ref "DEV1_J1") (pin "4") (pinfunction "4_4") (pintype "passive"))
    )
    (net (code "161") (name "unconnected-(DEV1_J1-Pad5)") (class "Default")
      (node (ref "DEV1_J1") (pin "5") (pinfunction "5_5") (pintype "passive"))
    )
    (net (code "162") (name "unconnected-(DEV1_J1-Pad6)") (class "Default")
      (node (ref "DEV1_J1") (pin "6") (pinfunction "6_6") (pintype "passive"))
    )
    (net (code "163") (name "unconnected-(DEV1_J1-Pad7)") (class "Default")
      (node (ref "DEV1_J1") (pin "7") (pinfunction "7_7") (pintype "passive"))
    )
    (net (code "164") (name "unconnected-(DEV1_J1-Pad8)") (class "Default")
      (node (ref "DEV1_J1") (pin "8") (pinfunction "8_8") (pintype "passive"))
    )
    (net (code "165") (name "unconnected-(DEV1_J1-Pad9)") (class "Default")
      (node (ref "DEV1_J1") (pin "9") (pinfunction "9_9") (pintype "passive"))
    )
    (net (code "166") (name "unconnected-(DEV1_J1-Pad10)") (class "Default")
      (node (ref "DEV1_J1") (pin "10") (pinfunction "10_10") (pintype "passive"))
    )
    (net (code "167") (name "unconnected-(DEV1_J1-Pad11)") (class "Default")
      (node (ref "DEV1_J1") (pin "11") (pinfunction "11_11") (pintype "passive"))
    )
    (net (code "168") (name "unconnected-(DEV1_J1-Pad12)") (class "Default")
      (node (ref "DEV1_J1") (pin "12") (pinfunction "12_12") (pintype "passive"))
    )
    (net (code "169") (name "unconnected-(DEV1_J1-Pad13)") (class "Default")
      (node (ref "DEV1_J1") (pin "13") (pinfunction "13_13") (pintype "passive"))
    )
    (net (code "170") (name "unconnected-(DEV1_J1-Pad14)") (class "Default")
      (node (ref "DEV1_J1") (pin "14") (pinfunction "14_14") (pintype "passive"))
    )
    (net (code "171") (name "unconnected-(DEV1_J1-Pad16)") (class "Default")
      (node (ref "DEV1_J1") (pin "16") (pinfunction "16_16") (pintype "passive"))
    )
    (net (code "172") (name "unconnected-(DEV1_J1-Pad17)") (class "Default")
      (node (ref "DEV1_J1") (pin "17") (pinfunction "17_17") (pintype "passive"))
    )
    (net (code "173") (name "unconnected-(DEV1_J1-Pad18)") (class "Default")
      (node (ref "DEV1_J1") (pin "18") (pinfunction "18_18") (pintype "passive"))
    )
    (net (code "174") (name "unconnected-(DEV1_J1-Pad19)") (class "Default")
      (node (ref "DEV1_J1") (pin "19") (pinfunction "19_19") (pintype "passive"))
    )
    (net (code "175") (name "unconnected-(DEV1_J1-Pad20)") (class "Default")
      (node (ref "DEV1_J1") (pin "20") (pinfunction "20_20") (pintype "passive"))
    )
    (net (code "176") (name "unconnected-(DEV1_J2-Pad1)") (class "Default")
      (node (ref "DEV1_J2") (pin "1") (pinfunction "1_1") (pintype "passive"))
    )
    (net (code "177") (name "unconnected-(DEV1_J2-Pad2)") (class "Default")
      (node (ref "DEV1_J2") (pin "2") (pinfunction "2_2") (pintype "passive"))
    )
    (net (code "178") (name "unconnected-(DEV1_J2-Pad5)") (class "Default")
      (node (ref "DEV1_J2") (pin "5") (pinfunction "5_5") (pintype "passive"))
    )
    (net (code "179") (name "unconnected-(DEV1_J2-Pad6)") (class "Default")
      (node (ref "DEV1_J2") (pin "6") (pinfunction "6_6") (pintype "passive"))
    )
    (net (code "180") (name "unconnected-(DEV1_J2-Pad8)") (class "Default")
      (node (ref "DEV1_J2") (pin "8") (pinfunction "8_8") (pintype "passive"))
    )
    (net (code "181") (name "unconnected-(DEV1_J2-Pad9)") (class "Default")
      (node (ref "DEV1_J2") (pin "9") (pinfunction "9_9") (pintype "passive"))
    )
    (net (code "182") (name "unconnected-(DEV1_J2-Pad12)") (class "Default")
      (node (ref "DEV1_J2") (pin "12") (pinfunction "12_12") (pintype "passive"))
    )
    (net (code "183") (name "unconnected-(DEV1_J2-Pad13)") (class "Default")
      (node (ref "DEV1_J2") (pin "13") (pinfunction "13_13") (pintype "passive"))
    )
    (net (code "184") (name "unconnected-(DEV1_J2-Pad14)") (class "Default")
      (node (ref "DEV1_J2") (pin "14") (pinfunction "14_14") (pintype "passive"))
    )
    (net (code "185") (name "unconnected-(DEV1_J2-Pad15)") (class "Default")
      (node (ref "DEV1_J2") (pin "15") (pinfunction "15_15") (pintype "passive"))
    )
    (net (code "186") (name "unconnected-(DEV1_J2-Pad16)") (class "Default")
      (node (ref "DEV1_J2") (pin "16") (pinfunction "16_16") (pintype "passive"))
    )
    (net (code "187") (name "unconnected-(DEV1_J2-Pad17)") (class "Default")
      (node (ref "DEV1_J2") (pin "17") (pinfunction "17_17") (pintype "passive"))
    )
    (net (code "188") (name "unconnected-(DEV1_J2-Pad18)") (class "Default")
      (node (ref "DEV1_J2") (pin "18") (pinfunction "18_18") (pintype "passive"))
    )
    (net (code "189") (name "unconnected-(DEV1_J2-Pad19)") (class "Default")
      (node (ref "DEV1_J2") (pin "19") (pinfunction "19_19") (pintype "passive"))
    )
    (net (code "190") (name "unconnected-(DEV1_J2-Pad20)") (class "Default")
      (node (ref "DEV1_J2") (pin "20") (pinfunction "20_20") (pintype "passive"))
    )
    (net (code "191") (name "unconnected-(DEV1_J3-Pad1)") (class "Default")
      (node (ref "DEV1_J3") (pin "1") (pinfunction "1_1") (pintype "passive"))
    )
    (net (code "192") (name "unconnected-(DEV1_J3-Pad2)") (class "Default")
      (node (ref "DEV1_J3") (pin "2") (pinfunction "2_2") (pintype "passive"))
    )
    (net (code "193") (name "unconnected-(DEV1_J3-Pad7)") (class "Default")
      (node (ref "DEV1_J3") (pin "7") (pinfunction "7_7") (pintype "passive"))
    )
    (net (code "194") (name "unconnected-(DEV1_J3-Pad8)") (class "Default")
      (node (ref "DEV1_J3") (pin "8") (pinfunction "8_8") (pintype "passive"))
    )
    (net (code "195") (name "unconnected-(DEV1_J3-Pad9)") (class "Default")
      (node (ref "DEV1_J3") (pin "9") (pinfunction "9_9") (pintype "passive"))
    )
    (net (code "196") (name "unconnected-(DEV2_J1-Pad1)") (class "Default")
      (node (ref "DEV2_J1") (pin "1") (pinfunction "1_1") (pintype "passive"))
    )
    (net (code "197") (name "unconnected-(DEV2_J1-Pad2)") (class "Default")
      (node (ref "DEV2_J1") (pin "2") (pinfunction "2_2") (pintype "passive"))
    )
    (net (code "198") (name "unconnected-(DEV2_J1-Pad3)") (class "Default")
      (node (ref "DEV2_J1") (pin "3") (pinfunction "3_3") (pintype "passive"))
    )
    (net (code "199") (name "unconnected-(DEV2_J1-Pad4)") (class "Default")
      (node (ref "DEV2_J1") (pin "4") (pinfunction "4_4") (pintype "passive"))
    )
    (net (code "200") (name "unconnected-(DEV2_J1-Pad5)") (class "Default")
      (node (ref "DEV2_J1") (pin "5") (pinfunction "5_5") (pintype "passive"))
    )
    (net (code "201") (name "unconnected-(DEV2_J1-Pad6)") (class "Default")
      (node (ref "DEV2_J1") (pin "6") (pinfunction "6_6") (pintype "passive"))
    )
    (net (code "202") (name "unconnected-(DEV2_J1-Pad7)") (class "Default")
      (node (ref "DEV2_J1") (pin "7") (pinfunction "7_7") (pintype "passive"))
    )
    (net (code "203") (name "unconnected-(DEV2_J1-Pad8)") (class "Default")
      (node (ref "DEV2_J1") (pin "8") (pinfunction "8_8") (pintype "passive"))
    )
    (net (code "204") (name "unconnected-(DEV2_J1-Pad9)") (class "Default")
      (node (ref "DEV2_J1") (pin "9") (pinfunction "9_9") (pintype "passive"))
    )
    (net (code "205") (name "unconnected-(DEV2_J1-Pad10)") (class "Default")
      (node (ref "DEV2_J1") (pin "10") (pinfunction "10_10") (pintype "passive"))
    )
    (net (code "206") (name "unconnected-(DEV2_J1-Pad11)") (class "Default")
      (node (ref "DEV2_J1") (pin "11") (pinfunction "11_11") (pintype "passive"))
    )
    (net (code "207") (name "unconnected-(DEV2_J1-Pad12)") (class "Default")
      (node (ref "DEV2_J1") (pin "12") (pinfunction "12_12") (pintype "passive"))
    )
    (net (code "208") (name "unconnected-(DEV2_J1-Pad13)") (class "Default")
      (node (ref "DEV2_J1") (pin "13") (pinfunction "13_13") (pintype "passive"))
    )
    (net (code "209") (name "unconnected-(DEV2_J1-Pad14)") (class "Default")
      (node (ref "DEV2_J1") (pin "14") (pinfunction "14_14") (pintype "passive"))
    )
    (net (code "210") (name "unconnected-(DEV2_J1-Pad16)") (class "Default")
      (node (ref "DEV2_J1") (pin "16") (pinfunction "16_16") (pintype "passive"))
    )
    (net (code "211") (name "unconnected-(DEV2_J1-Pad17)") (class "Default")
      (node (ref "DEV2_J1") (pin "17") (pinfunction "17_17") (pintype "passive"))
    )
    (net (code "212") (name "unconnected-(DEV2_J1-Pad18)") (class "Default")
      (node (ref "DEV2_J1") (pin "18") (pinfunction "18_18") (pintype "passive"))
    )
    (net (code "213") (name "unconnected-(DEV2_J1-Pad19)") (class "Default")
      (node (ref "DEV2_J1") (pin "19") (pinfunction "19_19") (pintype "passive"))
    )
    (net (code "214") (name "unconnected-(DEV2_J1-Pad20)") (class "Default")
      (node (ref "DEV2_J1") (pin "20") (pinfunction "20_20") (pintype "passive"))
    )
    (net (code "215") (name "unconnected-(DEV2_J2-Pad1)") (class "Default")
      (node (ref "DEV2_J2") (pin "1") (pinfunction "1_1") (pintype "passive"))
    )
    (net (code "216") (name "unconnected-(DEV2_J2-Pad2)") (class "Default")
      (node (ref "DEV2_J2") (pin "2") (pinfunction "2_2") (pintype "passive"))
    )
    (net (code "217") (name "unconnected-(DEV2_J2-Pad5)") (class "Default")
      (node (ref "DEV2_J2") (pin "5") (pinfunction "5_5") (pintype "passive"))
    )
    (net (code "218") (name "unconnected-(DEV2_J2-Pad6)") (class "Default")
      (node (ref "DEV2_J2") (pin "6") (pinfunction "6_6") (pintype "passive"))
    )
    (net (code "219") (name "unconnected-(DEV2_J2-Pad8)") (class "Default")
      (node (ref "DEV2_J2") (pin "8") (pinfunction "8_8") (pintype "passive"))
    )
    (net (code "220") (name "unconnected-(DEV2_J2-Pad9)") (class "Default")
      (node (ref "DEV2_J2") (pin "9") (pinfunction "9_9") (pintype "passive"))
    )
    (net (code "221") (name "unconnected-(DEV2_J2-Pad12)") (class "Default")
      (node (ref "DEV2_J2") (pin "12") (pinfunction "12_12") (pintype "passive"))
    )
    (net (code "222") (name "unconnected-(DEV2_J2-Pad13)") (class "Default")
      (node (ref "DEV2_J2") (pin "13") (pinfunction "13_13") (pintype "passive"))
    )
    (net (code "223") (name "unconnected-(DEV2_J2-Pad14)") (class "Default")
      (node (ref "DEV2_J2") (pin "14") (pinfunction "14_14") (pintype "passive"))
    )
    (net (code "224") (name "unconnected-(DEV2_J2-Pad15)") (class "Default")
      (node (ref "DEV2_J2") (pin "15") (pinfunction "15_15") (pintype "passive"))
    )
    (net (code "225") (name "unconnected-(DEV2_J2-Pad16)") (class "Default")
      (node (ref "DEV2_J2") (pin "16") (pinfunction "16_16") (pintype "passive"))
    )
    (net (code "226") (name "unconnected-(DEV2_J2-Pad17)") (class "Default")
      (node (ref "DEV2_J2") (pin "17") (pinfunction "17_17") (pintype "passive"))
    )
    (net (code "227") (name "unconnected-(DEV2_J2-Pad18)") (class "Default")
      (node (ref "DEV2_J2") (pin "18") (pinfunction "18_18") (pintype "passive"))
    )
    (net (code "228") (name "unconnected-(DEV2_J2-Pad19)") (class "Default")
      (node (ref "DEV2_J2") (pin "19") (pinfunction "19_19") (pintype "passive"))
    )
    (net (code "229") (name "unconnected-(DEV2_J2-Pad20)") (class "Default")
      (node (ref "DEV2_J2") (pin "20") (pinfunction "20_20") (pintype "passive"))
    )
    (net (code "230") (name "unconnected-(DEV2_J3-Pad1)") (class "Default")
      (node (ref "DEV2_J3") (pin "1") (pinfunction "1_1") (pintype "passive"))
    )
    (net (code "231") (name "unconnected-(DEV2_J3-Pad2)") (class "Default")
      (node (ref "DEV2_J3") (pin "2") (pinfunction "2_2") (pintype "passive"))
    )
    (net (code "232") (name "unconnected-(DEV2_J3-Pad7)") (class "Default")
      (node (ref "DEV2_J3") (pin "7") (pinfunction "7_7") (pintype "passive"))
    )
    (net (code "233") (name "unconnected-(DEV2_J3-Pad8)") (class "Default")
      (node (ref "DEV2_J3") (pin "8") (pinfunction "8_8") (pintype "passive"))
    )
    (net (code "234") (name "unconnected-(DEV2_J3-Pad9)") (class "Default")
      (node (ref "DEV2_J3") (pin "9") (pinfunction "9_9") (pintype "passive"))
    )
    (net (code "235") (name "unconnected-(SD-Pad1)") (class "Default")
      (node (ref "SD") (pin "1") (pinfunction "1_1") (pintype "passive"))
    )
    (net (code "236") (name "unconnected-(SD-Pad2)") (class "Default")
      (node (ref "SD") (pin "2") (pinfunction "2_2") (pintype "passive"))
    )
  )
)
